# project2.net
KiCad netlist of a schematic drawn in EAGLE
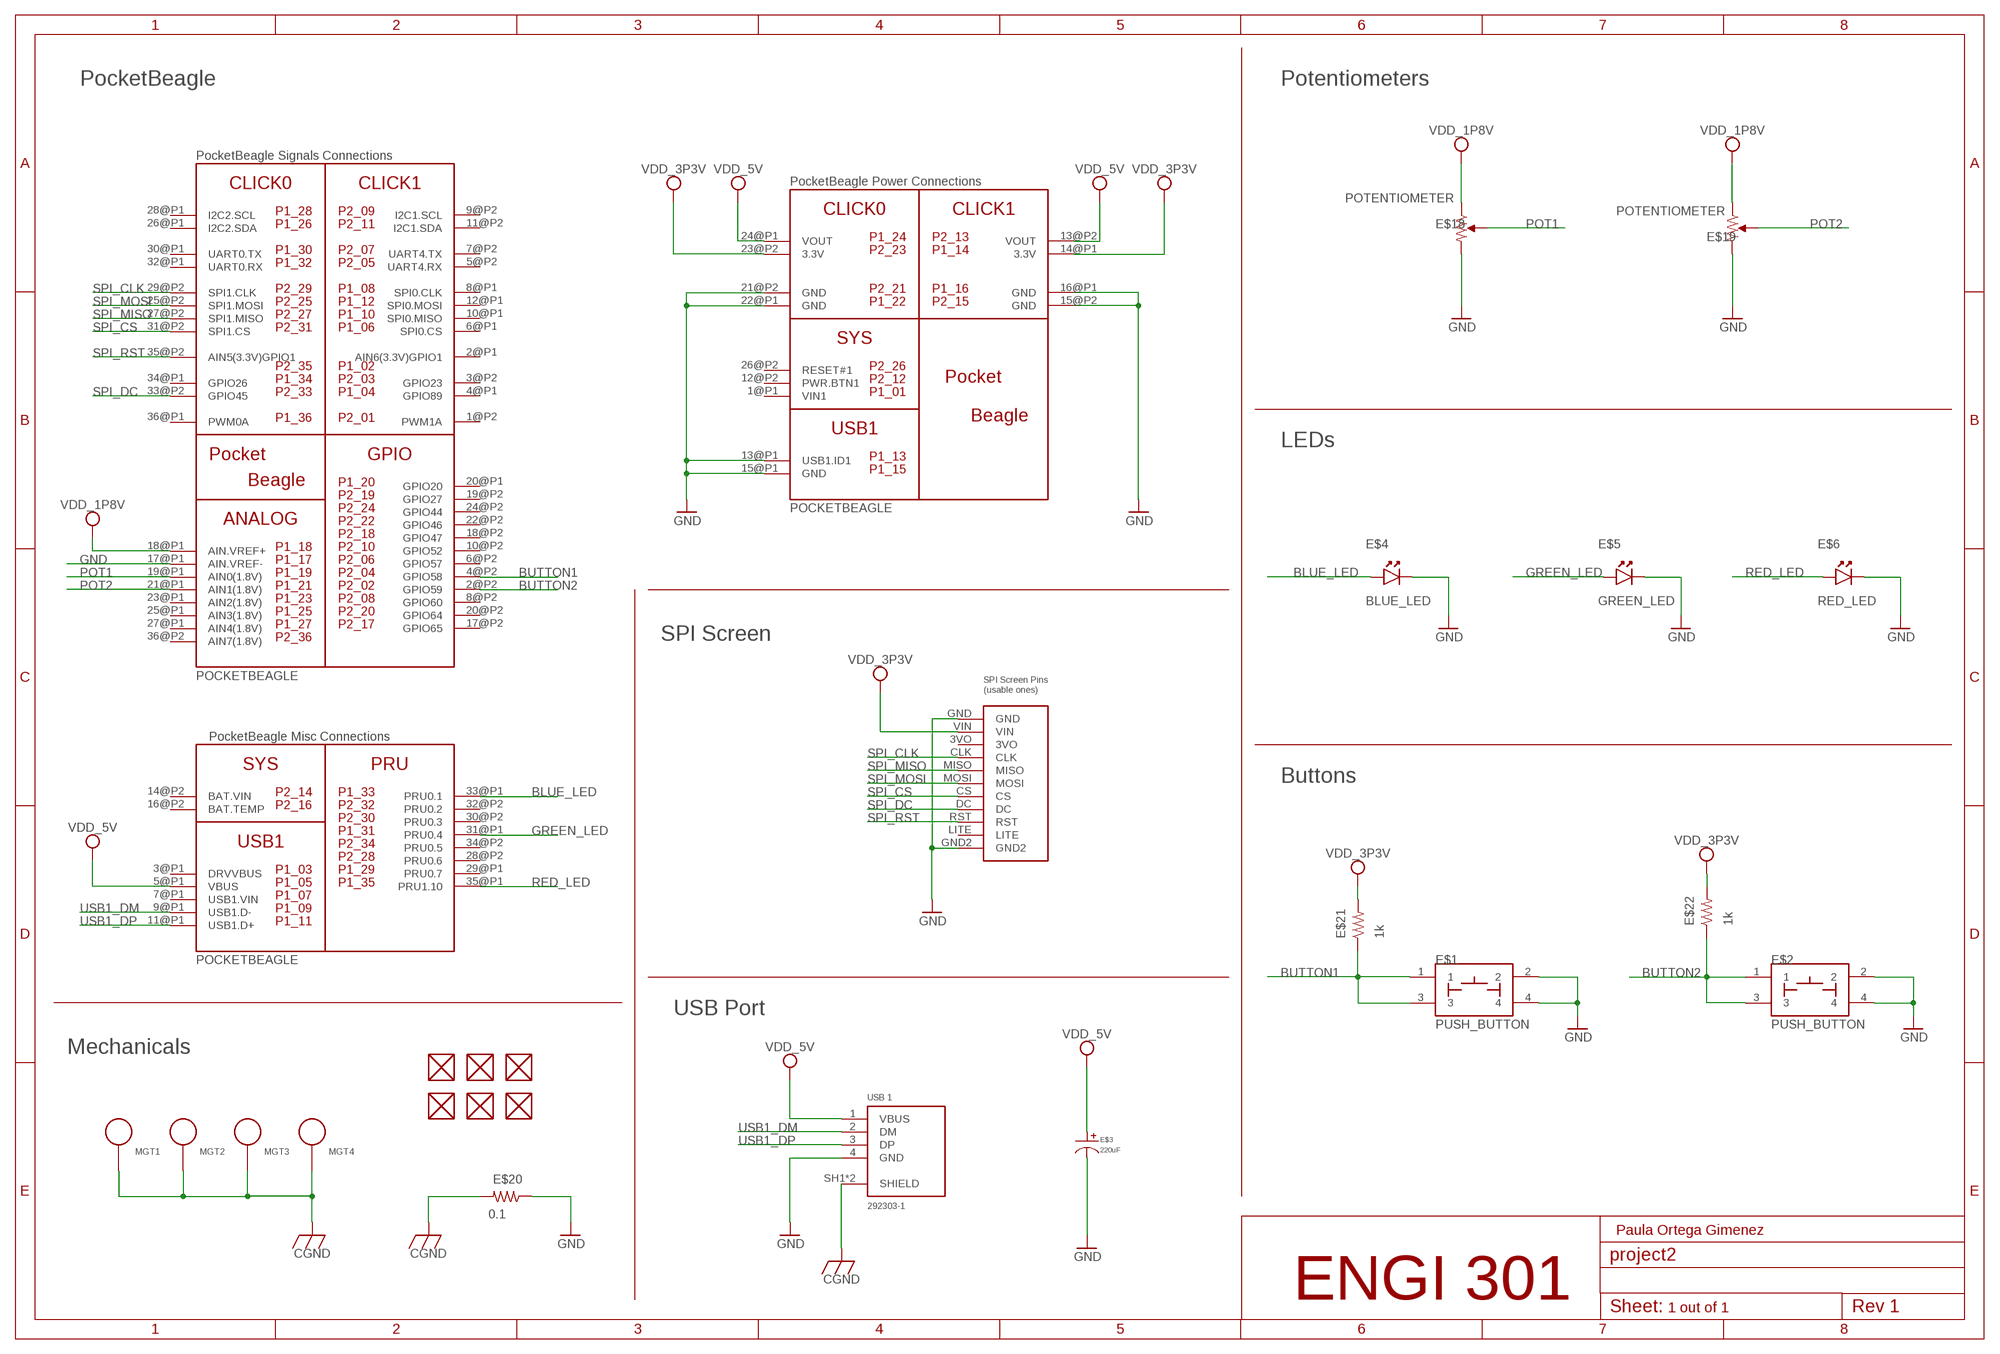
[diagram p0: schematic, sheet 1]

(export (version "E")
  (design (tool "Eeschema 10.0.6"))
  (components
    (comp (ref "E$1")
      (value "PUSH_BUTTON")
      (footprint "eagle-import:BUTTON_12.5MM")
      (libsource (lib "eagle-import") (part "PUSH_BUTTON"))
    )
    (comp (ref "E$2")
      (value "PUSH_BUTTON")
      (footprint "eagle-import:BUTTON_12.5MM")
      (libsource (lib "eagle-import") (part "PUSH_BUTTON"))
    )
    (comp (ref "E$3")
      (value "220uF")
      (footprint "eagle-import:CP10MM")
      (libsource (lib "eagle-import") (part "CAPACITOR_P_10MM"))
    )
    (comp (ref "E$4")
      (value "BLUE_LED")
      (footprint "eagle-import:EIA-STD")
      (libsource (lib "eagle-import") (part "LED"))
    )
    (comp (ref "E$5")
      (value "GREEN_LED")
      (footprint "eagle-import:EIA-STD")
      (libsource (lib "eagle-import") (part "LED"))
    )
    (comp (ref "E$6")
      (value "RED_LED")
      (footprint "eagle-import:EIA-STD")
      (libsource (lib "eagle-import") (part "LED"))
    )
    (comp (ref "E$18")
      (value "POTENTIOMETER")
      (footprint "eagle-import:POT-PO90S")
      (libsource (lib "eagle-import") (part "POTENTIOMETER"))
    )
    (comp (ref "E$19")
      (value "POTENTIOMETER")
      (footprint "eagle-import:POT-PO90S")
      (libsource (lib "eagle-import") (part "POTENTIOMETER"))
    )
    (comp (ref "E$20")
      (value "0.1")
      (footprint "eagle-import:R0805")
      (libsource (lib "eagle-import") (part "R_R0805"))
    )
    (comp (ref "E$21")
      (value "1k")
      (footprint "eagle-import:R0805")
      (libsource (lib "eagle-import") (part "R_R0805"))
    )
    (comp (ref "E$22")
      (value "1k")
      (footprint "eagle-import:R0805")
      (libsource (lib "eagle-import") (part "R_R0805"))
    )
    (comp (ref "E$24")
      (value "292303-1")
      (footprint "eagle-import:TE_292303-1")
      (fields (field (name "DIGIKEY_PART_NUMBER") "A31726-ND") (field (name "MF") "TE Connectivity"))
      (libsource (lib "eagle-import") (part "292303-1"))
    )
    (comp (ref "FUD1")
      (value "FIDUCIAL")
      (footprint "eagle-import:FIDUCIAL_40MIL")
      (libsource (lib "eagle-import") (part "FIDUCIAL"))
    )
    (comp (ref "FUD2")
      (value "FIDUCIAL")
      (footprint "eagle-import:FIDUCIAL_40MIL")
      (libsource (lib "eagle-import") (part "FIDUCIAL"))
    )
    (comp (ref "FUD3")
      (value "FIDUCIAL")
      (footprint "eagle-import:FIDUCIAL_40MIL")
      (libsource (lib "eagle-import") (part "FIDUCIAL"))
    )
    (comp (ref "FUD4")
      (value "FIDUCIAL")
      (footprint "eagle-import:FIDUCIAL_40MIL")
      (libsource (lib "eagle-import") (part "FIDUCIAL"))
    )
    (comp (ref "FUD5")
      (value "FIDUCIAL")
      (footprint "eagle-import:FIDUCIAL_40MIL")
      (libsource (lib "eagle-import") (part "FIDUCIAL"))
    )
    (comp (ref "FUD6")
      (value "FIDUCIAL")
      (footprint "eagle-import:FIDUCIAL_40MIL")
      (libsource (lib "eagle-import") (part "FIDUCIAL"))
    )
    (comp (ref "MGT1")
      (value "MOUNTING_HOLE")
      (footprint "eagle-import:MOUNTING_HOLE")
      (libsource (lib "eagle-import") (part "MOUNTING_HOLE"))
    )
    (comp (ref "MGT2")
      (value "MOUNTING_HOLE")
      (footprint "eagle-import:MOUNTING_HOLE")
      (libsource (lib "eagle-import") (part "MOUNTING_HOLE"))
    )
    (comp (ref "MGT3")
      (value "MOUNTING_HOLE")
      (footprint "eagle-import:MOUNTING_HOLE")
      (libsource (lib "eagle-import") (part "MOUNTING_HOLE"))
    )
    (comp (ref "MGT4")
      (value "MOUNTING_HOLE")
      (footprint "eagle-import:MOUNTING_HOLE")
      (libsource (lib "eagle-import") (part "MOUNTING_HOLE"))
    )
    (comp (ref "U$1")
      (value "POCKETBEAGLE")
      (footprint "eagle-import:POCKETBEAGLE")
      (libsource (lib "eagle-import") (part "POCKETBEAGLE"))
    )
    (comp (ref "U1")
      (value "SPI")
      (footprint "eagle-import:SPI")
      (libsource (lib "eagle-import") (part "SPI"))
    )
  )
  (nets
    (net (code "1") (name "/BAT.VIN") (class "Default")
      (node (ref "U$1") (pin "14@P2") (pinfunction "BAT.VIN_14@P2") (pintype "power_in"))
    )
    (net (code "2") (name "/BLUE_LED") (class "Default")
      (node (ref "E$4") (pin "ANODE") (pinfunction "ANODE_ANODE") (pintype "bidirectional"))
      (node (ref "U$1") (pin "33@P1") (pinfunction "PRU0.1_33@P1") (pintype "bidirectional"))
    )
    (net (code "3") (name "/BUTTON1") (class "Default")
      (node (ref "E$1") (pin "1") (pinfunction "1_1") (pintype "bidirectional"))
      (node (ref "E$1") (pin "3") (pinfunction "3_3") (pintype "bidirectional"))
      (node (ref "E$21") (pin "1") (pinfunction "1_1") (pintype "passive"))
      (node (ref "U$1") (pin "4@P2") (pinfunction "GPIO58_4@P2") (pintype "bidirectional"))
    )
    (net (code "4") (name "/BUTTON2") (class "Default")
      (node (ref "E$2") (pin "1") (pinfunction "1_1") (pintype "bidirectional"))
      (node (ref "E$2") (pin "3") (pinfunction "3_3") (pintype "bidirectional"))
      (node (ref "E$22") (pin "1") (pinfunction "1_1") (pintype "passive"))
      (node (ref "U$1") (pin "2@P2") (pinfunction "GPIO59_2@P2") (pintype "bidirectional"))
    )
    (net (code "5") (name "/GREEN_LED") (class "Default")
      (node (ref "E$5") (pin "ANODE") (pinfunction "ANODE_ANODE") (pintype "bidirectional"))
      (node (ref "U$1") (pin "31@P1") (pinfunction "PRU0.4_31@P1") (pintype "bidirectional"))
    )
    (net (code "6") (name "/POT1") (class "Default")
      (node (ref "E$18") (pin "S") (pinfunction "S_S") (pintype "bidirectional"))
      (node (ref "U$1") (pin "19@P1") (pinfunction "AIN0(1.8V)_19@P1") (pintype "input"))
    )
    (net (code "7") (name "/POT2") (class "Default")
      (node (ref "E$19") (pin "S") (pinfunction "S_S") (pintype "bidirectional"))
      (node (ref "U$1") (pin "21@P1") (pinfunction "AIN1(1.8V)_21@P1") (pintype "input"))
    )
    (net (code "8") (name "/RED_LED") (class "Default")
      (node (ref "E$6") (pin "ANODE") (pinfunction "ANODE_ANODE") (pintype "bidirectional"))
      (node (ref "U$1") (pin "35@P1") (pinfunction "PRU1.10_35@P1") (pintype "bidirectional"))
    )
    (net (code "9") (name "/SPI_CLK") (class "Default")
      (node (ref "U$1") (pin "29@P2") (pinfunction "SPI1.CLK_29@P2") (pintype "bidirectional"))
      (node (ref "U1") (pin "CLK") (pinfunction "CLK_CLK") (pintype "bidirectional"))
    )
    (net (code "10") (name "/SPI_CS") (class "Default")
      (node (ref "U$1") (pin "31@P2") (pinfunction "SPI1.CS_31@P2") (pintype "bidirectional"))
      (node (ref "U1") (pin "CS") (pinfunction "CS_CS") (pintype "bidirectional"))
    )
    (net (code "11") (name "/SPI_DC") (class "Default")
      (node (ref "U$1") (pin "33@P2") (pinfunction "GPIO45_33@P2") (pintype "bidirectional"))
      (node (ref "U1") (pin "DC") (pinfunction "DC_DC") (pintype "bidirectional"))
    )
    (net (code "12") (name "/SPI_MISO") (class "Default")
      (node (ref "U$1") (pin "27@P2") (pinfunction "SPI1.MISO_27@P2") (pintype "bidirectional"))
      (node (ref "U1") (pin "MISO") (pinfunction "MISO_MISO") (pintype "bidirectional"))
    )
    (net (code "13") (name "/SPI_MOSI") (class "Default")
      (node (ref "U$1") (pin "25@P2") (pinfunction "SPI1.MOSI_25@P2") (pintype "bidirectional"))
      (node (ref "U1") (pin "MOSI") (pinfunction "MOSI_MOSI") (pintype "bidirectional"))
    )
    (net (code "14") (name "/SPI_RST") (class "Default")
      (node (ref "U$1") (pin "35@P2") (pinfunction "AIN5(3.3V)GPIO1_35@P2") (pintype "bidirectional"))
      (node (ref "U1") (pin "RST") (pinfunction "RST_RST") (pintype "bidirectional"))
    )
    (net (code "15") (name "/USB1_DM") (class "Default")
      (node (ref "E$24") (pin "2") (pinfunction "DM_2") (pintype "passive"))
      (node (ref "U$1") (pin "9@P1") (pinfunction "USB1.D-_9@P1") (pintype "bidirectional"))
    )
    (net (code "16") (name "/USB1_DP") (class "Default")
      (node (ref "E$24") (pin "3") (pinfunction "DP_3") (pintype "passive"))
      (node (ref "U$1") (pin "11@P1") (pinfunction "USB1.D+_11@P1") (pintype "bidirectional"))
    )
    (net (code "17") (name "/VIN1") (class "Default")
      (node (ref "U$1") (pin "1@P1") (pinfunction "VIN1_1@P1") (pintype "power_in"))
    )
    (net (code "18") (name "CGND") (class "Default")
      (node (ref "E$20") (pin "2") (pinfunction "2_2") (pintype "passive"))
      (node (ref "E$24") (pin "SH1") (pinfunction "SHIELD_SH1") (pintype "passive"))
      (node (ref "E$24") (pin "SH2") (pinfunction "SHIELD_SH2") (pintype "passive"))
      (node (ref "MGT1") (pin "P$1") (pinfunction "P$1_P$1") (pintype "bidirectional"))
      (node (ref "MGT2") (pin "P$1") (pinfunction "P$1_P$1") (pintype "bidirectional"))
      (node (ref "MGT3") (pin "P$1") (pinfunction "P$1_P$1") (pintype "bidirectional"))
      (node (ref "MGT4") (pin "P$1") (pinfunction "P$1_P$1") (pintype "bidirectional"))
    )
    (net (code "19") (name "GND") (class "Default")
      (node (ref "E$1") (pin "2") (pinfunction "2_2") (pintype "bidirectional"))
      (node (ref "E$1") (pin "4") (pinfunction "4_4") (pintype "bidirectional"))
      (node (ref "E$18") (pin "CW") (pinfunction "CW_CW") (pintype "passive"))
      (node (ref "E$19") (pin "CW") (pinfunction "CW_CW") (pintype "passive"))
      (node (ref "E$2") (pin "2") (pinfunction "2_2") (pintype "bidirectional"))
      (node (ref "E$2") (pin "4") (pinfunction "4_4") (pintype "bidirectional"))
      (node (ref "E$20") (pin "1") (pinfunction "1_1") (pintype "passive"))
      (node (ref "E$24") (pin "4") (pinfunction "GND_4") (pintype "passive"))
      (node (ref "E$3") (pin "P$2") (pinfunction "P$2_P$2") (pintype "passive"))
      (node (ref "E$4") (pin "CATHODE") (pinfunction "CATHODE_CATHODE") (pintype "bidirectional"))
      (node (ref "E$5") (pin "CATHODE") (pinfunction "CATHODE_CATHODE") (pintype "bidirectional"))
      (node (ref "E$6") (pin "CATHODE") (pinfunction "CATHODE_CATHODE") (pintype "bidirectional"))
      (node (ref "U$1") (pin "13@P1") (pinfunction "USB1.ID1_13@P1") (pintype "bidirectional"))
      (node (ref "U$1") (pin "15@P1") (pinfunction "GND_15@P1") (pintype "bidirectional"))
      (node (ref "U$1") (pin "15@P2") (pinfunction "GND_15@P2") (pintype "power_in"))
      (node (ref "U$1") (pin "16@P1") (pinfunction "GND_16@P1") (pintype "power_in"))
      (node (ref "U$1") (pin "17@P1") (pinfunction "AIN.VREF-_17@P1") (pintype "input"))
      (node (ref "U$1") (pin "21@P2") (pinfunction "GND_21@P2") (pintype "power_in"))
      (node (ref "U$1") (pin "22@P1") (pinfunction "GND_22@P1") (pintype "power_in"))
      (node (ref "U1") (pin "GND") (pinfunction "GND_GND") (pintype "bidirectional"))
      (node (ref "U1") (pin "GND2") (pinfunction "GND2_GND2") (pintype "bidirectional"))
    )
    (net (code "20") (name "VDD_1P8V") (class "Default")
      (node (ref "E$18") (pin "CCW") (pinfunction "CCW_CCW") (pintype "passive"))
      (node (ref "E$19") (pin "CCW") (pinfunction "CCW_CCW") (pintype "passive"))
      (node (ref "U$1") (pin "18@P1") (pinfunction "AIN.VREF+_18@P1") (pintype "input"))
    )
    (net (code "21") (name "VDD_3P3V") (class "Default")
      (node (ref "E$21") (pin "2") (pinfunction "2_2") (pintype "passive"))
      (node (ref "E$22") (pin "2") (pinfunction "2_2") (pintype "passive"))
      (node (ref "U$1") (pin "14@P1") (pinfunction "3.3V_14@P1") (pintype "power_in"))
      (node (ref "U$1") (pin "23@P2") (pinfunction "3.3V_23@P2") (pintype "power_in"))
      (node (ref "U1") (pin "VIN") (pinfunction "VIN_VIN") (pintype "bidirectional"))
    )
    (net (code "22") (name "VDD_5V") (class "Default")
      (node (ref "E$24") (pin "1") (pinfunction "VBUS_1") (pintype "passive"))
      (node (ref "E$3") (pin "P$1") (pinfunction "P$1_P$1") (pintype "passive"))
      (node (ref "U$1") (pin "13@P2") (pinfunction "VOUT_13@P2") (pintype "power_in"))
      (node (ref "U$1") (pin "24@P1") (pinfunction "VOUT_24@P1") (pintype "power_in"))
      (node (ref "U$1") (pin "5@P1") (pinfunction "VBUS_5@P1") (pintype "bidirectional"))
    )
    (net (code "23") (name "unconnected-(FUD1-PadP$1)") (class "Default")
      (node (ref "FUD1") (pin "P$1") (pinfunction "P$1_P$1") (pintype "no_connect"))
    )
    (net (code "24") (name "unconnected-(FUD2-PadP$1)") (class "Default")
      (node (ref "FUD2") (pin "P$1") (pinfunction "P$1_P$1") (pintype "no_connect"))
    )
    (net (code "25") (name "unconnected-(FUD3-PadP$1)") (class "Default")
      (node (ref "FUD3") (pin "P$1") (pinfunction "P$1_P$1") (pintype "no_connect"))
    )
    (net (code "26") (name "unconnected-(FUD4-PadP$1)") (class "Default")
      (node (ref "FUD4") (pin "P$1") (pinfunction "P$1_P$1") (pintype "no_connect"))
    )
    (net (code "27") (name "unconnected-(FUD5-PadP$1)") (class "Default")
      (node (ref "FUD5") (pin "P$1") (pinfunction "P$1_P$1") (pintype "no_connect"))
    )
    (net (code "28") (name "unconnected-(FUD6-PadP$1)") (class "Default")
      (node (ref "FUD6") (pin "P$1") (pinfunction "P$1_P$1") (pintype "no_connect"))
    )
    (net (code "29") (name "unconnected-(U$1A-BAT.TEMP-Pad16@P2)") (class "Default")
      (node (ref "U$1") (pin "16@P2") (pinfunction "BAT.TEMP_16@P2") (pintype "input"))
    )
    (net (code "30") (name "unconnected-(U$1A-DRVVBUS-Pad3@P1)") (class "Default")
      (node (ref "U$1") (pin "3@P1") (pinfunction "DRVVBUS_3@P1") (pintype "bidirectional"))
    )
    (net (code "31") (name "unconnected-(U$1A-PRU0.2-Pad32@P2)") (class "Default")
      (node (ref "U$1") (pin "32@P2") (pinfunction "PRU0.2_32@P2") (pintype "bidirectional"))
    )
    (net (code "32") (name "unconnected-(U$1A-PRU0.3-Pad30@P2)") (class "Default")
      (node (ref "U$1") (pin "30@P2") (pinfunction "PRU0.3_30@P2") (pintype "bidirectional"))
    )
    (net (code "33") (name "unconnected-(U$1A-PRU0.5-Pad34@P2)") (class "Default")
      (node (ref "U$1") (pin "34@P2") (pinfunction "PRU0.5_34@P2") (pintype "bidirectional"))
    )
    (net (code "34") (name "unconnected-(U$1A-PRU0.6-Pad28@P2)") (class "Default")
      (node (ref "U$1") (pin "28@P2") (pinfunction "PRU0.6_28@P2") (pintype "bidirectional"))
    )
    (net (code "35") (name "unconnected-(U$1A-PRU0.7-Pad29@P1)") (class "Default")
      (node (ref "U$1") (pin "29@P1") (pinfunction "PRU0.7_29@P1") (pintype "bidirectional"))
    )
    (net (code "36") (name "unconnected-(U$1A-USB1.VIN-Pad7@P1)") (class "Default")
      (node (ref "U$1") (pin "7@P1") (pinfunction "USB1.VIN_7@P1") (pintype "bidirectional"))
    )
    (net (code "37") (name "unconnected-(U$1B-PWR.BTN1-Pad12@P2)") (class "Default")
      (node (ref "U$1") (pin "12@P2") (pinfunction "PWR.BTN1_12@P2") (pintype "input"))
    )
    (net (code "38") (name "unconnected-(U$1B-RESET#1-Pad26@P2)") (class "Default")
      (node (ref "U$1") (pin "26@P2") (pinfunction "RESET#1_26@P2") (pintype "input"))
    )
    (net (code "39") (name "unconnected-(U$1C-AIN2(1.8V)-Pad23@P1)") (class "Default")
      (node (ref "U$1") (pin "23@P1") (pinfunction "AIN2(1.8V)_23@P1") (pintype "input"))
    )
    (net (code "40") (name "unconnected-(U$1C-AIN3(1.8V)-Pad25@P1)") (class "Default")
      (node (ref "U$1") (pin "25@P1") (pinfunction "AIN3(1.8V)_25@P1") (pintype "input"))
    )
    (net (code "41") (name "unconnected-(U$1C-AIN4(1.8V)-Pad27@P1)") (class "Default")
      (node (ref "U$1") (pin "27@P1") (pinfunction "AIN4(1.8V)_27@P1") (pintype "input"))
    )
    (net (code "42") (name "unconnected-(U$1C-AIN6(3.3V)GPIO1-Pad2@P1)") (class "Default")
      (node (ref "U$1") (pin "2@P1") (pinfunction "AIN6(3.3V)GPIO1_2@P1") (pintype "bidirectional"))
    )
    (net (code "43") (name "unconnected-(U$1C-AIN7(1.8V)-Pad36@P2)") (class "Default")
      (node (ref "U$1") (pin "36@P2") (pinfunction "AIN7(1.8V)_36@P2") (pintype "input"))
    )
    (net (code "44") (name "unconnected-(U$1C-GPIO20-Pad20@P1)") (class "Default")
      (node (ref "U$1") (pin "20@P1") (pinfunction "GPIO20_20@P1") (pintype "bidirectional"))
    )
    (net (code "45") (name "unconnected-(U$1C-GPIO23-Pad3@P2)") (class "Default")
      (node (ref "U$1") (pin "3@P2") (pinfunction "GPIO23_3@P2") (pintype "bidirectional"))
    )
    (net (code "46") (name "unconnected-(U$1C-GPIO26-Pad34@P1)") (class "Default")
      (node (ref "U$1") (pin "34@P1") (pinfunction "GPIO26_34@P1") (pintype "bidirectional"))
    )
    (net (code "47") (name "unconnected-(U$1C-GPIO27-Pad19@P2)") (class "Default")
      (node (ref "U$1") (pin "19@P2") (pinfunction "GPIO27_19@P2") (pintype "bidirectional"))
    )
    (net (code "48") (name "unconnected-(U$1C-GPIO44-Pad24@P2)") (class "Default")
      (node (ref "U$1") (pin "24@P2") (pinfunction "GPIO44_24@P2") (pintype "bidirectional"))
    )
    (net (code "49") (name "unconnected-(U$1C-GPIO46-Pad22@P2)") (class "Default")
      (node (ref "U$1") (pin "22@P2") (pinfunction "GPIO46_22@P2") (pintype "bidirectional"))
    )
    (net (code "50") (name "unconnected-(U$1C-GPIO47-Pad18@P2)") (class "Default")
      (node (ref "U$1") (pin "18@P2") (pinfunction "GPIO47_18@P2") (pintype "bidirectional"))
    )
    (net (code "51") (name "unconnected-(U$1C-GPIO52-Pad10@P2)") (class "Default")
      (node (ref "U$1") (pin "10@P2") (pinfunction "GPIO52_10@P2") (pintype "bidirectional"))
    )
    (net (code "52") (name "unconnected-(U$1C-GPIO57-Pad6@P2)") (class "Default")
      (node (ref "U$1") (pin "6@P2") (pinfunction "GPIO57_6@P2") (pintype "bidirectional"))
    )
    (net (code "53") (name "unconnected-(U$1C-GPIO60-Pad8@P2)") (class "Default")
      (node (ref "U$1") (pin "8@P2") (pinfunction "GPIO60_8@P2") (pintype "bidirectional"))
    )
    (net (code "54") (name "unconnected-(U$1C-GPIO64-Pad20@P2)") (class "Default")
      (node (ref "U$1") (pin "20@P2") (pinfunction "GPIO64_20@P2") (pintype "bidirectional"))
    )
    (net (code "55") (name "unconnected-(U$1C-GPIO65-Pad17@P2)") (class "Default")
      (node (ref "U$1") (pin "17@P2") (pinfunction "GPIO65_17@P2") (pintype "bidirectional"))
    )
    (net (code "56") (name "unconnected-(U$1C-GPIO89-Pad4@P1)") (class "Default")
      (node (ref "U$1") (pin "4@P1") (pinfunction "GPIO89_4@P1") (pintype "bidirectional"))
    )
    (net (code "57") (name "unconnected-(U$1C-I2C1.SCL-Pad9@P2)") (class "Default")
      (node (ref "U$1") (pin "9@P2") (pinfunction "I2C1.SCL_9@P2") (pintype "bidirectional"))
    )
    (net (code "58") (name "unconnected-(U$1C-I2C1.SDA-Pad11@P2)") (class "Default")
      (node (ref "U$1") (pin "11@P2") (pinfunction "I2C1.SDA_11@P2") (pintype "bidirectional"))
    )
    (net (code "59") (name "unconnected-(U$1C-I2C2.SCL-Pad28@P1)") (class "Default")
      (node (ref "U$1") (pin "28@P1") (pinfunction "I2C2.SCL_28@P1") (pintype "bidirectional"))
    )
    (net (code "60") (name "unconnected-(U$1C-I2C2.SDA-Pad26@P1)") (class "Default")
      (node (ref "U$1") (pin "26@P1") (pinfunction "I2C2.SDA_26@P1") (pintype "bidirectional"))
    )
    (net (code "61") (name "unconnected-(U$1C-PWM0A-Pad36@P1)") (class "Default")
      (node (ref "U$1") (pin "36@P1") (pinfunction "PWM0A_36@P1") (pintype "bidirectional"))
    )
    (net (code "62") (name "unconnected-(U$1C-PWM1A-Pad1@P2)") (class "Default")
      (node (ref "U$1") (pin "1@P2") (pinfunction "PWM1A_1@P2") (pintype "bidirectional"))
    )
    (net (code "63") (name "unconnected-(U$1C-SPI0.CLK-Pad8@P1)") (class "Default")
      (node (ref "U$1") (pin "8@P1") (pinfunction "SPI0.CLK_8@P1") (pintype "bidirectional"))
    )
    (net (code "64") (name "unconnected-(U$1C-SPI0.CS-Pad6@P1)") (class "Default")
      (node (ref "U$1") (pin "6@P1") (pinfunction "SPI0.CS_6@P1") (pintype "bidirectional"))
    )
    (net (code "65") (name "unconnected-(U$1C-SPI0.MISO-Pad10@P1)") (class "Default")
      (node (ref "U$1") (pin "10@P1") (pinfunction "SPI0.MISO_10@P1") (pintype "bidirectional"))
    )
    (net (code "66") (name "unconnected-(U$1C-SPI0.MOSI-Pad12@P1)") (class "Default")
      (node (ref "U$1") (pin "12@P1") (pinfunction "SPI0.MOSI_12@P1") (pintype "bidirectional"))
    )
    (net (code "67") (name "unconnected-(U$1C-UART0.RX-Pad32@P1)") (class "Default")
      (node (ref "U$1") (pin "32@P1") (pinfunction "UART0.RX_32@P1") (pintype "bidirectional"))
    )
    (net (code "68") (name "unconnected-(U$1C-UART0.TX-Pad30@P1)") (class "Default")
      (node (ref "U$1") (pin "30@P1") (pinfunction "UART0.TX_30@P1") (pintype "bidirectional"))
    )
    (net (code "69") (name "unconnected-(U$1C-UART4.RX-Pad5@P2)") (class "Default")
      (node (ref "U$1") (pin "5@P2") (pinfunction "UART4.RX_5@P2") (pintype "bidirectional"))
    )
    (net (code "70") (name "unconnected-(U$1C-UART4.TX-Pad7@P2)") (class "Default")
      (node (ref "U$1") (pin "7@P2") (pinfunction "UART4.TX_7@P2") (pintype "bidirectional"))
    )
    (net (code "71") (name "unconnected-(U1-Pad3VO)") (class "Default")
      (node (ref "U1") (pin "3VO") (pinfunction "3VO_3VO") (pintype "bidirectional"))
    )
    (net (code "72") (name "unconnected-(U1-PadLITE)") (class "Default")
      (node (ref "U1") (pin "LITE") (pinfunction "LITE_LITE") (pintype "bidirectional"))
    )
  )
)
